# Digital_Output_A.net
KiCad netlist of a schematic drawn in EAGLE
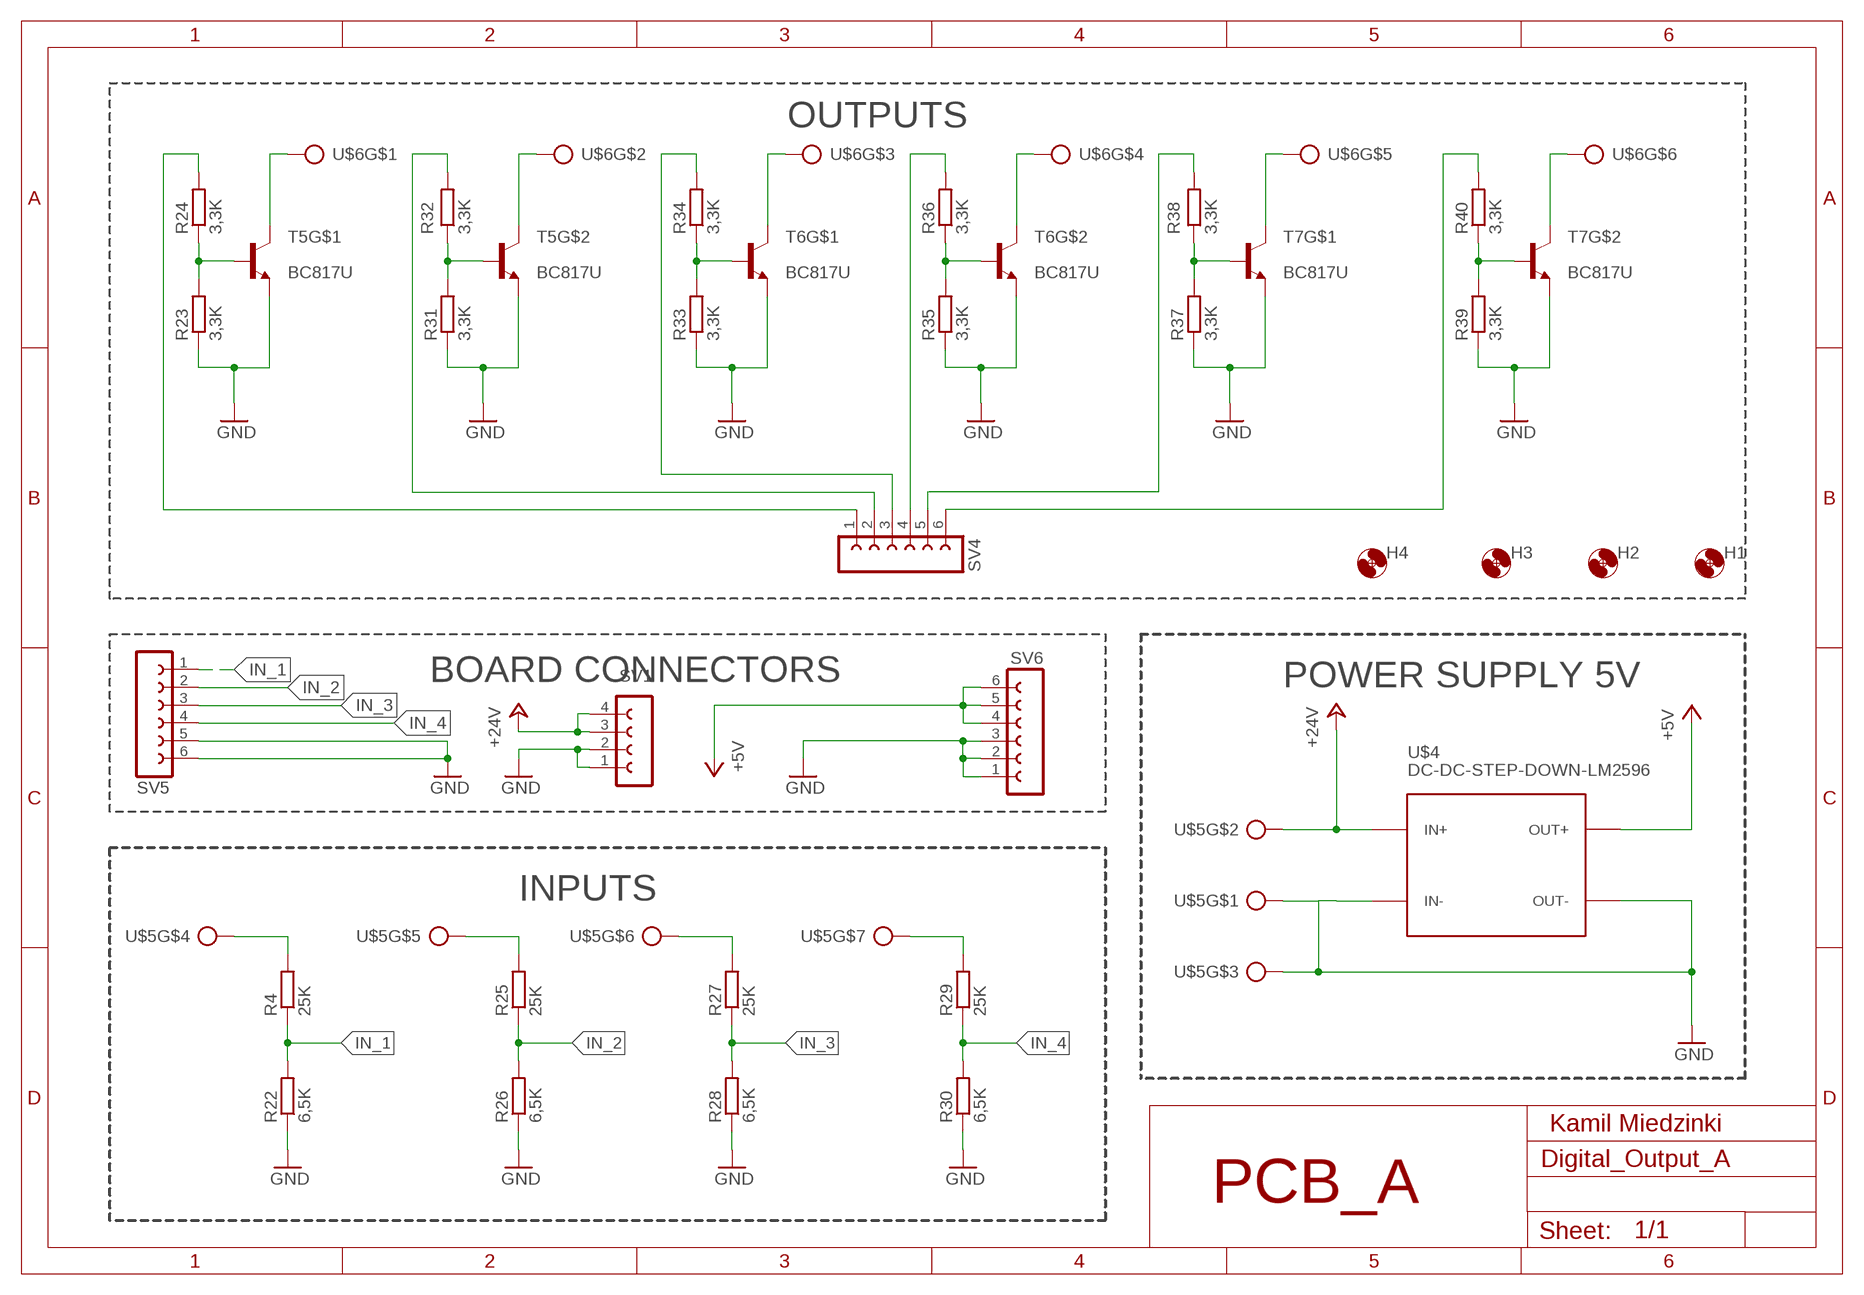
[diagram p0: schematic, sheet 1]

(export (version "E")
  (design (tool "Eeschema 10.0.6"))
  (components
    (comp (ref "H1")
      (value "MOUNT-HOLE3.3")
      (footprint "eagle-import:3,3")
      (libsource (lib "eagle-import") (part "MOUNT-HOLE3.3"))
    )
    (comp (ref "H2")
      (value "MOUNT-HOLE3.3")
      (footprint "eagle-import:3,3")
      (libsource (lib "eagle-import") (part "MOUNT-HOLE3.3"))
    )
    (comp (ref "H3")
      (value "MOUNT-HOLE3.3")
      (footprint "eagle-import:3,3")
      (libsource (lib "eagle-import") (part "MOUNT-HOLE3.3"))
    )
    (comp (ref "H4")
      (value "MOUNT-HOLE3.3")
      (footprint "eagle-import:3,3")
      (libsource (lib "eagle-import") (part "MOUNT-HOLE3.3"))
    )
    (comp (ref "R4")
      (value "25K")
      (footprint "eagle-import:0204_7")
      (libsource (lib "eagle-import") (part "R-EU_0204/7"))
    )
    (comp (ref "R22")
      (value "6,5K")
      (footprint "eagle-import:0204_7")
      (libsource (lib "eagle-import") (part "R-EU_0204/7"))
    )
    (comp (ref "R23")
      (value "3,3K")
      (footprint "eagle-import:0204_7")
      (libsource (lib "eagle-import") (part "R-EU_0204/7"))
    )
    (comp (ref "R24")
      (value "3,3K")
      (footprint "eagle-import:0204_7")
      (libsource (lib "eagle-import") (part "R-EU_0204/7"))
    )
    (comp (ref "R25")
      (value "25K")
      (footprint "eagle-import:0204_7")
      (libsource (lib "eagle-import") (part "R-EU_0204/7"))
    )
    (comp (ref "R26")
      (value "6,5K")
      (footprint "eagle-import:0204_7")
      (libsource (lib "eagle-import") (part "R-EU_0204/7"))
    )
    (comp (ref "R27")
      (value "25K")
      (footprint "eagle-import:0204_7")
      (libsource (lib "eagle-import") (part "R-EU_0204/7"))
    )
    (comp (ref "R28")
      (value "6,5K")
      (footprint "eagle-import:0204_7")
      (libsource (lib "eagle-import") (part "R-EU_0204/7"))
    )
    (comp (ref "R29")
      (value "25K")
      (footprint "eagle-import:0204_7")
      (libsource (lib "eagle-import") (part "R-EU_0204/7"))
    )
    (comp (ref "R30")
      (value "6,5K")
      (footprint "eagle-import:0204_7")
      (libsource (lib "eagle-import") (part "R-EU_0204/7"))
    )
    (comp (ref "R31")
      (value "3,3K")
      (footprint "eagle-import:0204_7")
      (libsource (lib "eagle-import") (part "R-EU_0204/7"))
    )
    (comp (ref "R32")
      (value "3,3K")
      (footprint "eagle-import:0204_7")
      (libsource (lib "eagle-import") (part "R-EU_0204/7"))
    )
    (comp (ref "R33")
      (value "3,3K")
      (footprint "eagle-import:0204_7")
      (libsource (lib "eagle-import") (part "R-EU_0204/7"))
    )
    (comp (ref "R34")
      (value "3,3K")
      (footprint "eagle-import:0204_7")
      (libsource (lib "eagle-import") (part "R-EU_0204/7"))
    )
    (comp (ref "R35")
      (value "3,3K")
      (footprint "eagle-import:0204_7")
      (libsource (lib "eagle-import") (part "R-EU_0204/7"))
    )
    (comp (ref "R36")
      (value "3,3K")
      (footprint "eagle-import:0204_7")
      (libsource (lib "eagle-import") (part "R-EU_0204/7"))
    )
    (comp (ref "R37")
      (value "3,3K")
      (footprint "eagle-import:0204_7")
      (libsource (lib "eagle-import") (part "R-EU_0204/7"))
    )
    (comp (ref "R38")
      (value "3,3K")
      (footprint "eagle-import:0204_7")
      (libsource (lib "eagle-import") (part "R-EU_0204/7"))
    )
    (comp (ref "R39")
      (value "3,3K")
      (footprint "eagle-import:0204_7")
      (libsource (lib "eagle-import") (part "R-EU_0204/7"))
    )
    (comp (ref "R40")
      (value "3,3K")
      (footprint "eagle-import:0204_7")
      (libsource (lib "eagle-import") (part "R-EU_0204/7"))
    )
    (comp (ref "SV1")
      (value "FE04-1")
      (footprint "eagle-import:FE04-1")
      (libsource (lib "eagle-import") (part "FE04-1"))
    )
    (comp (ref "SV4")
      (value "FE06-1")
      (footprint "eagle-import:FE06")
      (libsource (lib "eagle-import") (part "FE06-1"))
    )
    (comp (ref "SV5")
      (value "FE06-1")
      (footprint "eagle-import:FE06")
      (libsource (lib "eagle-import") (part "FE06-1"))
    )
    (comp (ref "SV6")
      (value "FE06-1")
      (footprint "eagle-import:FE06")
      (libsource (lib "eagle-import") (part "FE06-1"))
    )
    (comp (ref "T5")
      (value "BC817U")
      (footprint "eagle-import:INF-SC74")
      (libsource (lib "eagle-import") (part "BC817U"))
    )
    (comp (ref "T6")
      (value "BC817U")
      (footprint "eagle-import:INF-SC74")
      (libsource (lib "eagle-import") (part "BC817U"))
    )
    (comp (ref "T7")
      (value "BC817U")
      (footprint "eagle-import:INF-SC74")
      (libsource (lib "eagle-import") (part "BC817U"))
    )
    (comp (ref "U$4")
      (value "DC-DC-STEP-DOWN-LM2596")
      (footprint "eagle-import:DC-DC-STEP-DOWN-LM2596")
      (libsource (lib "eagle-import") (part "DC-DC-STEP-DOWN-LM2596"))
    )
    (comp (ref "U$5")
      (value "24V")
      (footprint "eagle-import:MKDSN2,5_7")
      (libsource (lib "eagle-import") (part "MKDSN2,5/7"))
    )
    (comp (ref "U$6")
      (value "MKDSN2,5/6")
      (footprint "eagle-import:MKDSN2,5_6")
      (libsource (lib "eagle-import") (part "MKDSN2,5/6"))
    )
  )
  (nets
    (net (code "1") (name "+5V") (class "Default")
      (node (ref "SV6") (pin "4") (pinfunction "4_4") (pintype "passive"))
      (node (ref "SV6") (pin "5") (pinfunction "5_5") (pintype "passive"))
      (node (ref "SV6") (pin "6") (pinfunction "6_6") (pintype "passive"))
      (node (ref "U$4") (pin "OUT+") (pinfunction "OUT+_OUT+") (pintype "bidirectional"))
    )
    (net (code "2") (name "+24V") (class "Default")
      (node (ref "SV1") (pin "3") (pinfunction "4_3") (pintype "passive"))
      (node (ref "SV1") (pin "4") (pinfunction "5_4") (pintype "passive"))
      (node (ref "U$4") (pin "IN+") (pinfunction "IN+_IN+") (pintype "bidirectional"))
      (node (ref "U$5") (pin "2") (pinfunction "KL_2") (pintype "passive"))
    )
    (net (code "3") (name "GND") (class "Default")
      (node (ref "R22") (pin "1") (pinfunction "1_1") (pintype "passive"))
      (node (ref "R23") (pin "1") (pinfunction "1_1") (pintype "passive"))
      (node (ref "R26") (pin "1") (pinfunction "1_1") (pintype "passive"))
      (node (ref "R28") (pin "1") (pinfunction "1_1") (pintype "passive"))
      (node (ref "R30") (pin "1") (pinfunction "1_1") (pintype "passive"))
      (node (ref "R31") (pin "1") (pinfunction "1_1") (pintype "passive"))
      (node (ref "R33") (pin "1") (pinfunction "1_1") (pintype "passive"))
      (node (ref "R35") (pin "1") (pinfunction "1_1") (pintype "passive"))
      (node (ref "R37") (pin "1") (pinfunction "1_1") (pintype "passive"))
      (node (ref "R39") (pin "1") (pinfunction "1_1") (pintype "passive"))
      (node (ref "SV1") (pin "1") (pinfunction "2_1") (pintype "passive"))
      (node (ref "SV1") (pin "2") (pinfunction "3_2") (pintype "passive"))
      (node (ref "SV5") (pin "5") (pinfunction "5_5") (pintype "passive"))
      (node (ref "SV5") (pin "6") (pinfunction "6_6") (pintype "passive"))
      (node (ref "SV6") (pin "1") (pinfunction "1_1") (pintype "passive"))
      (node (ref "SV6") (pin "2") (pinfunction "2_2") (pintype "passive"))
      (node (ref "SV6") (pin "3") (pinfunction "3_3") (pintype "passive"))
      (node (ref "T5") (pin "1") (pinfunction "E_1") (pintype "passive"))
      (node (ref "T5") (pin "4") (pinfunction "E_4") (pintype "passive"))
      (node (ref "T6") (pin "1") (pinfunction "E_1") (pintype "passive"))
      (node (ref "T6") (pin "4") (pinfunction "E_4") (pintype "passive"))
      (node (ref "T7") (pin "1") (pinfunction "E_1") (pintype "passive"))
      (node (ref "T7") (pin "4") (pinfunction "E_4") (pintype "passive"))
      (node (ref "U$4") (pin "IN-") (pinfunction "IN-_IN-") (pintype "bidirectional"))
      (node (ref "U$4") (pin "OUT-") (pinfunction "OUT-_OUT-") (pintype "bidirectional"))
      (node (ref "U$5") (pin "1") (pinfunction "KL_1") (pintype "passive"))
      (node (ref "U$5") (pin "3") (pinfunction "KL_3") (pintype "passive"))
    )
    (net (code "4") (name "IN_1") (class "Default")
      (node (ref "R22") (pin "2") (pinfunction "2_2") (pintype "passive"))
      (node (ref "R4") (pin "1") (pinfunction "1_1") (pintype "passive"))
      (node (ref "SV5") (pin "1") (pinfunction "1_1") (pintype "passive"))
    )
    (net (code "5") (name "IN_2") (class "Default")
      (node (ref "R25") (pin "1") (pinfunction "1_1") (pintype "passive"))
      (node (ref "R26") (pin "2") (pinfunction "2_2") (pintype "passive"))
      (node (ref "SV5") (pin "2") (pinfunction "2_2") (pintype "passive"))
    )
    (net (code "6") (name "IN_3") (class "Default")
      (node (ref "R27") (pin "1") (pinfunction "1_1") (pintype "passive"))
      (node (ref "R28") (pin "2") (pinfunction "2_2") (pintype "passive"))
      (node (ref "SV5") (pin "3") (pinfunction "3_3") (pintype "passive"))
    )
    (net (code "7") (name "IN_4") (class "Default")
      (node (ref "R29") (pin "1") (pinfunction "1_1") (pintype "passive"))
      (node (ref "R30") (pin "2") (pinfunction "2_2") (pintype "passive"))
      (node (ref "SV5") (pin "4") (pinfunction "4_4") (pintype "passive"))
    )
    (net (code "8") (name "Net-(R24-Pad2)") (class "Default")
      (node (ref "R24") (pin "2") (pinfunction "2_2") (pintype "passive"))
      (node (ref "SV4") (pin "1") (pinfunction "1_1") (pintype "passive"))
    )
    (net (code "9") (name "Net-(R32-Pad2)") (class "Default")
      (node (ref "R32") (pin "2") (pinfunction "2_2") (pintype "passive"))
      (node (ref "SV4") (pin "2") (pinfunction "2_2") (pintype "passive"))
    )
    (net (code "10") (name "Net-(R34-Pad2)") (class "Default")
      (node (ref "R34") (pin "2") (pinfunction "2_2") (pintype "passive"))
      (node (ref "SV4") (pin "3") (pinfunction "3_3") (pintype "passive"))
    )
    (net (code "11") (name "Net-(R36-Pad2)") (class "Default")
      (node (ref "R36") (pin "2") (pinfunction "2_2") (pintype "passive"))
      (node (ref "SV4") (pin "4") (pinfunction "4_4") (pintype "passive"))
    )
    (net (code "12") (name "Net-(R38-Pad2)") (class "Default")
      (node (ref "R38") (pin "2") (pinfunction "2_2") (pintype "passive"))
      (node (ref "SV4") (pin "5") (pinfunction "5_5") (pintype "passive"))
    )
    (net (code "13") (name "Net-(R40-Pad2)") (class "Default")
      (node (ref "R40") (pin "2") (pinfunction "2_2") (pintype "passive"))
      (node (ref "SV4") (pin "6") (pinfunction "6_6") (pintype "passive"))
    )
    (net (code "14") (name "Net-(T5A-B)") (class "Default")
      (node (ref "R23") (pin "2") (pinfunction "2_2") (pintype "passive"))
      (node (ref "R24") (pin "1") (pinfunction "1_1") (pintype "passive"))
      (node (ref "T5") (pin "2") (pinfunction "B_2") (pintype "passive"))
    )
    (net (code "15") (name "Net-(T5A-C)") (class "Default")
      (node (ref "T5") (pin "6") (pinfunction "C_6") (pintype "passive"))
      (node (ref "U$6") (pin "1") (pinfunction "KL_1") (pintype "passive"))
    )
    (net (code "16") (name "Net-(T5B-B)") (class "Default")
      (node (ref "R31") (pin "2") (pinfunction "2_2") (pintype "passive"))
      (node (ref "R32") (pin "1") (pinfunction "1_1") (pintype "passive"))
      (node (ref "T5") (pin "5") (pinfunction "B_5") (pintype "passive"))
    )
    (net (code "17") (name "Net-(T5B-C)") (class "Default")
      (node (ref "T5") (pin "3") (pinfunction "C_3") (pintype "passive"))
      (node (ref "U$6") (pin "2") (pinfunction "KL_2") (pintype "passive"))
    )
    (net (code "18") (name "Net-(T6A-B)") (class "Default")
      (node (ref "R33") (pin "2") (pinfunction "2_2") (pintype "passive"))
      (node (ref "R34") (pin "1") (pinfunction "1_1") (pintype "passive"))
      (node (ref "T6") (pin "2") (pinfunction "B_2") (pintype "passive"))
    )
    (net (code "19") (name "Net-(T6A-C)") (class "Default")
      (node (ref "T6") (pin "6") (pinfunction "C_6") (pintype "passive"))
      (node (ref "U$6") (pin "3") (pinfunction "KL_3") (pintype "passive"))
    )
    (net (code "20") (name "Net-(T6B-B)") (class "Default")
      (node (ref "R35") (pin "2") (pinfunction "2_2") (pintype "passive"))
      (node (ref "R36") (pin "1") (pinfunction "1_1") (pintype "passive"))
      (node (ref "T6") (pin "5") (pinfunction "B_5") (pintype "passive"))
    )
    (net (code "21") (name "Net-(T6B-C)") (class "Default")
      (node (ref "T6") (pin "3") (pinfunction "C_3") (pintype "passive"))
      (node (ref "U$6") (pin "4") (pinfunction "KL_4") (pintype "passive"))
    )
    (net (code "22") (name "Net-(T7A-B)") (class "Default")
      (node (ref "R37") (pin "2") (pinfunction "2_2") (pintype "passive"))
      (node (ref "R38") (pin "1") (pinfunction "1_1") (pintype "passive"))
      (node (ref "T7") (pin "2") (pinfunction "B_2") (pintype "passive"))
    )
    (net (code "23") (name "Net-(T7A-C)") (class "Default")
      (node (ref "T7") (pin "6") (pinfunction "C_6") (pintype "passive"))
      (node (ref "U$6") (pin "5") (pinfunction "KL_5") (pintype "passive"))
    )
    (net (code "24") (name "Net-(T7B-B)") (class "Default")
      (node (ref "R39") (pin "2") (pinfunction "2_2") (pintype "passive"))
      (node (ref "R40") (pin "1") (pinfunction "1_1") (pintype "passive"))
      (node (ref "T7") (pin "5") (pinfunction "B_5") (pintype "passive"))
    )
    (net (code "25") (name "Net-(T7B-C)") (class "Default")
      (node (ref "T7") (pin "3") (pinfunction "C_3") (pintype "passive"))
      (node (ref "U$6") (pin "6") (pinfunction "KL_6") (pintype "passive"))
    )
    (net (code "26") (name "Net-(U$5D-KL)") (class "Default")
      (node (ref "R4") (pin "2") (pinfunction "2_2") (pintype "passive"))
      (node (ref "U$5") (pin "4") (pinfunction "KL_4") (pintype "passive"))
    )
    (net (code "27") (name "Net-(U$5E-KL)") (class "Default")
      (node (ref "R25") (pin "2") (pinfunction "2_2") (pintype "passive"))
      (node (ref "U$5") (pin "5") (pinfunction "KL_5") (pintype "passive"))
    )
    (net (code "28") (name "Net-(U$5F-KL)") (class "Default")
      (node (ref "R27") (pin "2") (pinfunction "2_2") (pintype "passive"))
      (node (ref "U$5") (pin "6") (pinfunction "KL_6") (pintype "passive"))
    )
    (net (code "29") (name "Net-(U$5G-KL)") (class "Default")
      (node (ref "R29") (pin "2") (pinfunction "2_2") (pintype "passive"))
      (node (ref "U$5") (pin "7") (pinfunction "KL_7") (pintype "passive"))
    )
  )
)
